# schematic.net
KiCad netlist of a schematic drawn in Altium Designer
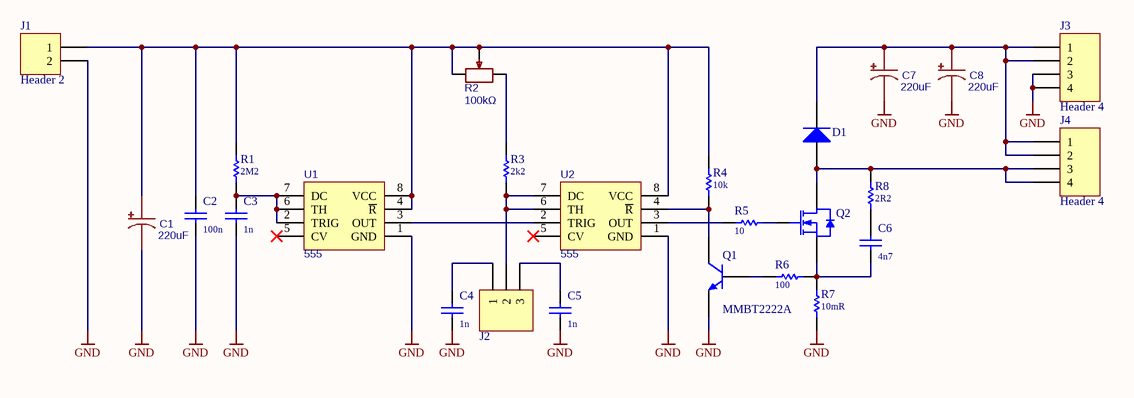
[diagram p0: schematic.SchDoc]

(export (version "E")
  (design (tool "Eeschema 10.0.6"))
  (components
    (comp (ref "C1")
      (value "220uF")
      (footprint "C7343")
      (libsource (lib "altium-import") (part "root_0_220uF_"))
    )
    (comp (ref "C2")
      (value "100n")
      (footprint "C0603")
      (libsource (lib "Miscellaneous Devices") (part "CAP"))
    )
    (comp (ref "C3") (value "1n") (footprint "C0603") (libsource (lib "Miscellaneous Devices") (part "CAP")))
    (comp (ref "C4") (value "1n") (footprint "C0603") (libsource (lib "Miscellaneous Devices") (part "CAP")))
    (comp (ref "C5") (value "1n") (footprint "C0603") (libsource (lib "Miscellaneous Devices") (part "CAP")))
    (comp (ref "C6") (value "4n7") (footprint "C0805") (libsource (lib "Miscellaneous Devices") (part "CAP")))
    (comp (ref "C7")
      (value "220uF")
      (footprint "CAP-TH_BD16.0-P7.50-D1.2-FD")
      (libsource (lib "altium-import") (part "root_0_220uF_"))
    )
    (comp (ref "C8")
      (value "220uF")
      (footprint "CAP-TH_BD16.0-P7.50-D1.2-FD")
      (libsource (lib "altium-import") (part "root_0_220uF_"))
    )
    (comp (ref "D1")
      (value "~")
      (footprint "SMB")
      (libsource (lib "Miscellaneous Devices") (part "US1M-13-F"))
    )
    (comp (ref "J1") (value "Header 2") (footprint "HDR-1X2") (libsource (lib "Schlib1") (part "Header 2")))
    (comp (ref "J2")
      (value "~")
      (footprint "HDR-1X3")
      (libsource (lib "Miscellaneous Devices") (part "Header 3"))
    )
    (comp (ref "J3") (value "Header 4") (footprint "HDR-1X4") (libsource (lib "Schlib1") (part "Header 4")))
    (comp (ref "J4") (value "Header 4") (footprint "HDR-1X4") (libsource (lib "Schlib1") (part "Header 4")))
    (comp (ref "Q1")
      (value "MMBT2222A")
      (footprint "SOT-23")
      (libsource (lib "Miscellaneous Devices") (part "MMBT2222ALT1G"))
    )
    (comp (ref "Q2")
      (value "~")
      (footprint "D2PAK")
      (libsource (lib "Miscellaneous Devices") (part "2N7002"))
    )
    (comp (ref "R1") (value "2M2") (footprint "R0603") (libsource (lib "RR_Passive") (part "RES")))
    (comp (ref "R2")
      (value "100kΩ")
      (footprint "RES-ADJ-TH_3362P-1-104LF")
      (description "3362P-1-104LF")
      (libsource (lib "altium-import") (part "root_3_100kΩ_"))
    )
    (comp (ref "R3") (value "2k2") (footprint "R0603") (libsource (lib "RR_Passive") (part "RES")))
    (comp (ref "R4") (value "10k") (footprint "R0603") (libsource (lib "RR_Passive") (part "RES")))
    (comp (ref "R5") (value "10") (footprint "R0603") (libsource (lib "RR_Passive") (part "RES")))
    (comp (ref "R6") (value "100") (footprint "R0603") (libsource (lib "RR_Passive") (part "RES")))
    (comp (ref "R7")
      (value "10mR")
      (footprint "R2512-WIDE")
      (libsource (lib "Miscellaneous Devices") (part "RES"))
    )
    (comp (ref "R8") (value "2R2") (footprint "R1206") (libsource (lib "RR_Passive") (part "RES")))
    (comp (ref "U1") (value "555") (footprint "SOIC-8") (libsource (lib "Schlib1") (part "555")))
    (comp (ref "U2") (value "555") (footprint "SOIC-8") (libsource (lib "Schlib1") (part "555")))
  )
  (nets
    (net (code "1") (name "GND") (class "Default")
      (node (ref "C1") (pin "2") (pinfunction "2_2") (pintype "passive"))
      (node (ref "C2") (pin "1") (pinfunction "1_1") (pintype "passive"))
      (node (ref "C3") (pin "1") (pinfunction "1_1") (pintype "passive"))
      (node (ref "C4") (pin "1") (pinfunction "1_1") (pintype "passive"))
      (node (ref "C5") (pin "1") (pinfunction "1_1") (pintype "passive"))
      (node (ref "C7") (pin "2") (pinfunction "2_2") (pintype "passive"))
      (node (ref "C8") (pin "2") (pinfunction "2_2") (pintype "passive"))
      (node (ref "J1") (pin "2") (pinfunction "2_2") (pintype "passive"))
      (node (ref "J3") (pin "3") (pinfunction "3_3") (pintype "passive"))
      (node (ref "J3") (pin "4") (pinfunction "4_4") (pintype "passive"))
      (node (ref "Q1") (pin "2") (pinfunction "E_2") (pintype "passive"))
      (node (ref "R7") (pin "1") (pinfunction "1_1") (pintype "passive"))
      (node (ref "U1") (pin "1") (pinfunction "GND_1") (pintype "passive"))
      (node (ref "U2") (pin "1") (pinfunction "GND_1") (pintype "passive"))
    )
    (net (code "2") (name "Net-(C4-Pad2)") (class "Default")
      (node (ref "C4") (pin "2") (pinfunction "2_2") (pintype "passive"))
      (node (ref "J2") (pin "1") (pinfunction "1_1") (pintype "passive"))
    )
    (net (code "3") (name "Net-(C5-Pad2)") (class "Default")
      (node (ref "C5") (pin "2") (pinfunction "2_2") (pintype "passive"))
      (node (ref "J2") (pin "3") (pinfunction "3_3") (pintype "passive"))
    )
    (net (code "4") (name "Net-(C6-Pad2)") (class "Default")
      (node (ref "C6") (pin "2") (pinfunction "2_2") (pintype "passive"))
      (node (ref "R8") (pin "1") (pinfunction "1_1") (pintype "passive"))
    )
    (net (code "5") (name "Net-(D1-A)") (class "Default")
      (node (ref "D1") (pin "1") (pinfunction "A_1") (pintype "passive"))
      (node (ref "J4") (pin "3") (pinfunction "3_3") (pintype "passive"))
      (node (ref "J4") (pin "4") (pinfunction "4_4") (pintype "passive"))
      (node (ref "Q2") (pin "2") (pinfunction "DRAIN_2") (pintype "passive"))
      (node (ref "R8") (pin "2") (pinfunction "2_2") (pintype "passive"))
    )
    (net (code "6") (name "Net-(D1-K)") (class "Default")
      (node (ref "C7") (pin "1") (pinfunction "1_1") (pintype "passive"))
      (node (ref "C8") (pin "1") (pinfunction "1_1") (pintype "passive"))
      (node (ref "D1") (pin "2") (pinfunction "K_2") (pintype "passive"))
      (node (ref "J3") (pin "1") (pinfunction "1_1") (pintype "passive"))
      (node (ref "J3") (pin "2") (pinfunction "2_2") (pintype "passive"))
      (node (ref "J4") (pin "1") (pinfunction "1_1") (pintype "passive"))
      (node (ref "J4") (pin "2") (pinfunction "2_2") (pintype "passive"))
    )
    (net (code "7") (name "Net-(Q1-B)") (class "Default")
      (node (ref "Q1") (pin "1") (pinfunction "B_1") (pintype "passive"))
      (node (ref "R6") (pin "2") (pinfunction "2_2") (pintype "passive"))
    )
    (net (code "8") (name "Net-(Q1-C)") (class "Default")
      (node (ref "Q1") (pin "3") (pinfunction "C_3") (pintype "passive"))
      (node (ref "R4") (pin "1") (pinfunction "1_1") (pintype "passive"))
      (node (ref "U2") (pin "4") (pinfunction "~{R}_4") (pintype "passive"))
    )
    (net (code "9") (name "Net-(Q2-GATE)") (class "Default")
      (node (ref "Q2") (pin "1") (pinfunction "GATE_1") (pintype "passive"))
      (node (ref "R5") (pin "1") (pinfunction "1_1") (pintype "passive"))
    )
    (net (code "10") (name "Net-(Q2-SOURCE)") (class "Default")
      (node (ref "C6") (pin "1") (pinfunction "1_1") (pintype "passive"))
      (node (ref "Q2") (pin "3") (pinfunction "SOURCE_3") (pintype "passive"))
      (node (ref "R6") (pin "1") (pinfunction "1_1") (pintype "passive"))
      (node (ref "R7") (pin "2") (pinfunction "2_2") (pintype "passive"))
    )
    (net (code "11") (name "Net-(R2-Pad1)") (class "Default")
      (node (ref "R2") (pin "1") (pinfunction "1_1") (pintype "passive"))
      (node (ref "R3") (pin "2") (pinfunction "2_2") (pintype "passive"))
    )
    (net (code "12") (name "Net-(U1-DC)") (class "Default")
      (node (ref "C3") (pin "2") (pinfunction "2_2") (pintype "passive"))
      (node (ref "R1") (pin "1") (pinfunction "1_1") (pintype "passive"))
      (node (ref "U1") (pin "2") (pinfunction "TRIG_2") (pintype "passive"))
      (node (ref "U1") (pin "6") (pinfunction "TH_6") (pintype "passive"))
      (node (ref "U1") (pin "7") (pinfunction "DC_7") (pintype "passive"))
    )
    (net (code "13") (name "Net-(U1-OUT)") (class "Default")
      (node (ref "U1") (pin "3") (pinfunction "OUT_3") (pintype "passive"))
      (node (ref "U2") (pin "2") (pinfunction "TRIG_2") (pintype "passive"))
    )
    (net (code "14") (name "Net-(U1-VCC)") (class "Default")
      (node (ref "C1") (pin "1") (pinfunction "1_1") (pintype "passive"))
      (node (ref "C2") (pin "2") (pinfunction "2_2") (pintype "passive"))
      (node (ref "J1") (pin "1") (pinfunction "1_1") (pintype "passive"))
      (node (ref "R1") (pin "2") (pinfunction "2_2") (pintype "passive"))
      (node (ref "R2") (pin "2") (pinfunction "2_2") (pintype "passive"))
      (node (ref "R2") (pin "3") (pinfunction "3_3") (pintype "passive"))
      (node (ref "R4") (pin "2") (pinfunction "2_2") (pintype "passive"))
      (node (ref "U1") (pin "4") (pinfunction "~{R}_4") (pintype "passive"))
      (node (ref "U1") (pin "8") (pinfunction "VCC_8") (pintype "passive"))
      (node (ref "U2") (pin "8") (pinfunction "VCC_8") (pintype "passive"))
    )
    (net (code "15") (name "Net-(U2-DC)") (class "Default")
      (node (ref "J2") (pin "2") (pinfunction "2_2") (pintype "passive"))
      (node (ref "R3") (pin "1") (pinfunction "1_1") (pintype "passive"))
      (node (ref "U2") (pin "6") (pinfunction "TH_6") (pintype "passive"))
      (node (ref "U2") (pin "7") (pinfunction "DC_7") (pintype "passive"))
    )
    (net (code "16") (name "Net-(U2-OUT)") (class "Default")
      (node (ref "R5") (pin "2") (pinfunction "2_2") (pintype "passive"))
      (node (ref "U2") (pin "3") (pinfunction "OUT_3") (pintype "passive"))
    )
    (net (code "17") (name "unconnected-(U1-CV-Pad5)") (class "Default")
      (node (ref "U1") (pin "5") (pinfunction "CV_5") (pintype "passive+no_connect"))
    )
    (net (code "18") (name "unconnected-(U2-CV-Pad5)") (class "Default")
      (node (ref "U2") (pin "5") (pinfunction "CV_5") (pintype "passive+no_connect"))
    )
  )
)
